# Schematic1.net
KiCad netlist of a schematic drawn in Altium Designer
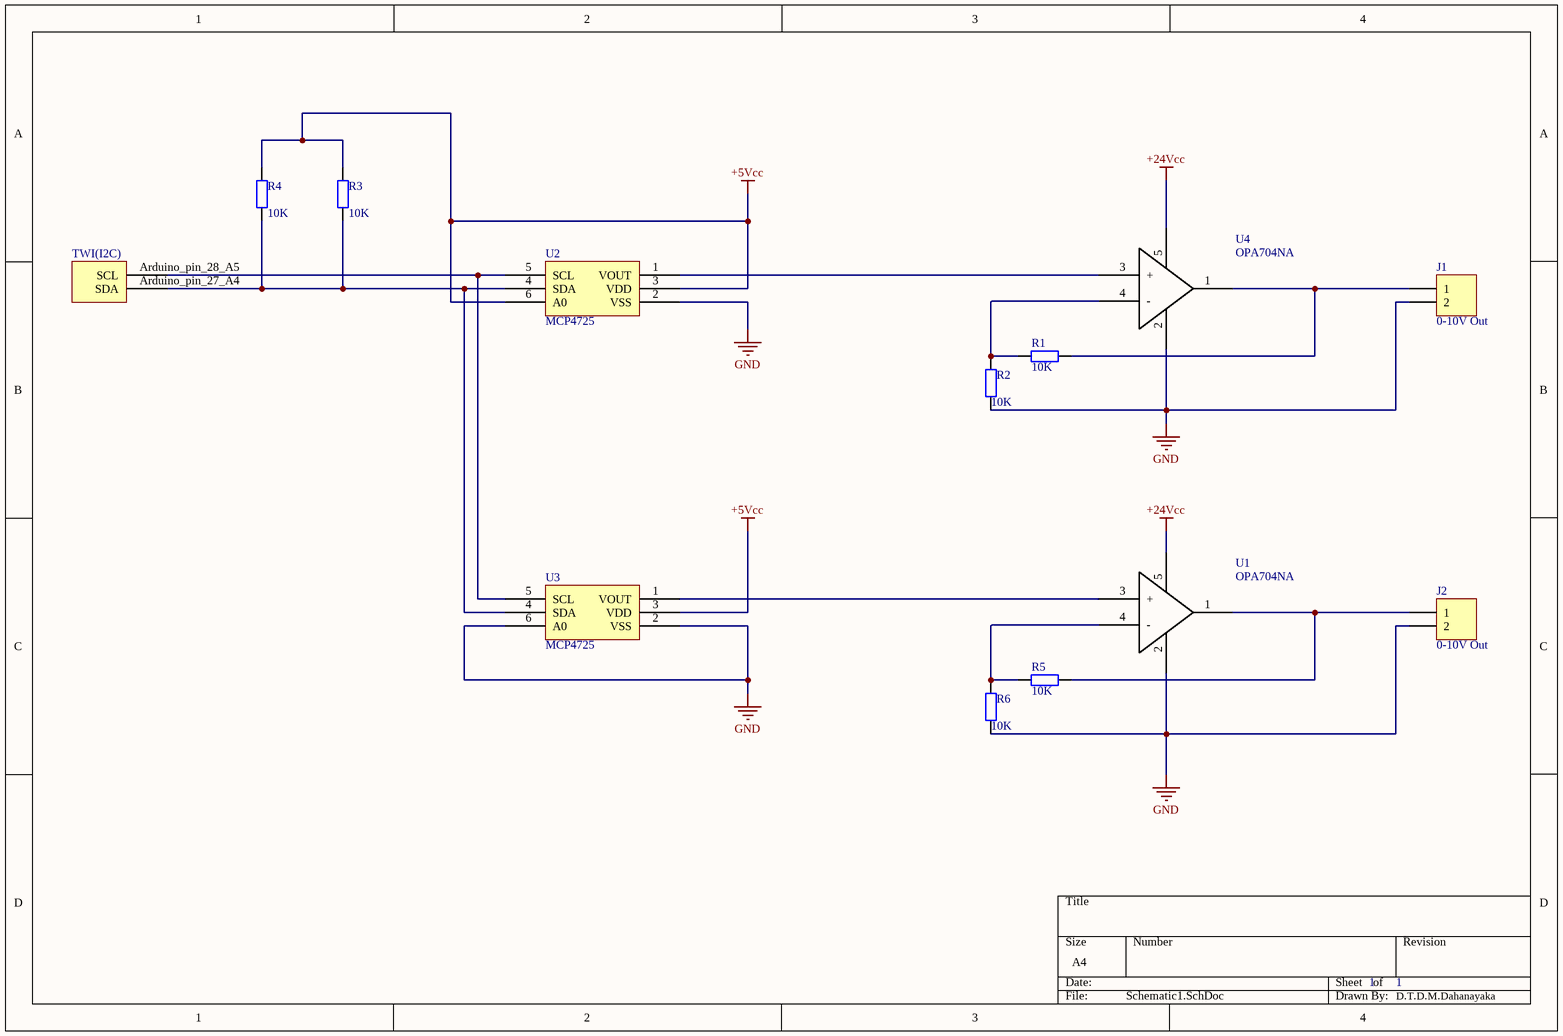
[diagram p0: Schematic1.SchDoc]

(export (version "E")
  (design (tool "Eeschema 10.0.6"))
  (components
    (comp (ref "J1")
      (value "0-10V Out")
      (footprint "HDR1X2")
      (description "Header, 2-Pin")
      (fields (field (name "PUBLISHER") "Altium Limited"))
      (libsource (lib "Miscellaneous Connectors") (part "Header 2"))
    )
    (comp (ref "J2")
      (value "0-10V Out")
      (footprint "HDR1X2")
      (description "Header, 2-Pin")
      (fields (field (name "PUBLISHER") "Altium Limited"))
      (libsource (lib "Miscellaneous Connectors") (part "Header 2"))
    )
    (comp (ref "R1")
      (value "10K")
      (footprint "AXIAL-0.4")
      (description "Resistor")
      (fields (field (name "Comment") "Res2") (field (name "PUBLISHER") "Altium Limited"))
      (libsource (lib "") (part "Res2_1"))
    )
    (comp (ref "R2")
      (value "10K")
      (footprint "AXIAL-0.4")
      (description "Resistor")
      (fields (field (name "Comment") "Res2") (field (name "PUBLISHER") "Altium Limited"))
      (libsource (lib "Miscellaneous Devices") (part "Res2"))
    )
    (comp (ref "R3")
      (value "10K")
      (footprint "AXIAL-0.4")
      (description "Resistor")
      (fields (field (name "Comment") "Res2") (field (name "PUBLISHER") "Altium Limited"))
      (libsource (lib "Miscellaneous Devices") (part "Res2"))
    )
    (comp (ref "R4")
      (value "10K")
      (footprint "AXIAL-0.4")
      (description "Resistor")
      (fields (field (name "Comment") "Res2") (field (name "PUBLISHER") "Altium Limited"))
      (libsource (lib "Miscellaneous Devices") (part "Res2"))
    )
    (comp (ref "R5")
      (value "10K")
      (footprint "AXIAL-0.4")
      (description "Resistor")
      (fields (field (name "Comment") "Res2") (field (name "PUBLISHER") "Altium Limited"))
      (libsource (lib "") (part "Res2_1"))
    )
    (comp (ref "R6")
      (value "10K")
      (footprint "AXIAL-0.4")
      (description "Resistor")
      (fields (field (name "Comment") "Res2") (field (name "PUBLISHER") "Altium Limited"))
      (libsource (lib "Miscellaneous Devices") (part "Res2"))
    )
    (comp (ref "TWI(I2C)")
      (value "Component_1")
      (libsource (lib "Arduino_mega_TWI_I2C") (part "Component_1"))
    )
    (comp (ref "U1") (value "OPA704NA") (libsource (lib "Op-Amp") (part "Component_1")))
    (comp (ref "U2") (value "MCP4725") (libsource (lib "MCP4725") (part "Component_1")))
    (comp (ref "U3") (value "MCP4725") (libsource (lib "MCP4725") (part "Component_1")))
    (comp (ref "U4") (value "OPA704NA") (libsource (lib "Op-Amp") (part "Component_1")))
  )
  (nets
    (net (code "1") (name "+5Vcc") (class "Default")
      (node (ref "R3") (pin "2") (pinfunction "2_2") (pintype "passive"))
      (node (ref "R4") (pin "2") (pinfunction "2_2") (pintype "passive"))
      (node (ref "U2") (pin "3") (pinfunction "VDD_3") (pintype "passive"))
      (node (ref "U2") (pin "6") (pinfunction "A0_6") (pintype "passive"))
      (node (ref "U3") (pin "3") (pinfunction "VDD_3") (pintype "passive"))
    )
    (net (code "2") (name "+24Vcc") (class "Default")
      (node (ref "U1") (pin "5") (pintype "passive"))
      (node (ref "U4") (pin "5") (pintype "passive"))
    )
    (net (code "3") (name "GND") (class "Default")
      (node (ref "J1") (pin "2") (pinfunction "2_2") (pintype "passive"))
      (node (ref "J2") (pin "2") (pinfunction "2_2") (pintype "passive"))
      (node (ref "R2") (pin "1") (pinfunction "1_1") (pintype "passive"))
      (node (ref "R6") (pin "1") (pinfunction "1_1") (pintype "passive"))
      (node (ref "U1") (pin "2") (pintype "passive"))
      (node (ref "U2") (pin "2") (pinfunction "VSS_2") (pintype "passive"))
      (node (ref "U3") (pin "2") (pinfunction "VSS_2") (pintype "passive"))
      (node (ref "U3") (pin "6") (pinfunction "A0_6") (pintype "passive"))
      (node (ref "U4") (pin "2") (pintype "passive"))
    )
    (net (code "4") (name "Net-(J1-Pad1)") (class "Default")
      (node (ref "J1") (pin "1") (pinfunction "1_1") (pintype "passive"))
      (node (ref "R1") (pin "1") (pinfunction "1_1") (pintype "passive"))
      (node (ref "U4") (pin "1") (pintype "passive"))
    )
    (net (code "5") (name "Net-(J2-Pad1)") (class "Default")
      (node (ref "J2") (pin "1") (pinfunction "1_1") (pintype "passive"))
      (node (ref "R5") (pin "1") (pinfunction "1_1") (pintype "passive"))
      (node (ref "U1") (pin "1") (pintype "passive"))
    )
    (net (code "6") (name "Net-(TWI(I2C)-SCL)") (class "Default")
      (node (ref "TWI(I2C)") (pin "Arduino_pin_28_A5") (pinfunction "SCL_Arduino_pin_28_A5") (pintype "passive"))
      (node (ref "U2") (pin "5") (pinfunction "SCL_5") (pintype "passive"))
      (node (ref "U3") (pin "5") (pinfunction "SCL_5") (pintype "passive"))
    )
    (net (code "7") (name "Net-(TWI(I2C)-SDA)") (class "Default")
      (node (ref "R3") (pin "1") (pinfunction "1_1") (pintype "passive"))
      (node (ref "R4") (pin "1") (pinfunction "1_1") (pintype "passive"))
      (node (ref "TWI(I2C)") (pin "Arduino_pin_27_A4") (pinfunction "SDA_Arduino_pin_27_A4") (pintype "passive"))
      (node (ref "U2") (pin "4") (pinfunction "SDA_4") (pintype "passive"))
      (node (ref "U3") (pin "4") (pinfunction "SDA_4") (pintype "passive"))
    )
    (net (code "8") (name "Net-(U1-+)") (class "Default")
      (node (ref "U1") (pin "3") (pinfunction "+_3") (pintype "passive"))
      (node (ref "U3") (pin "1") (pinfunction "VOUT_1") (pintype "passive"))
    )
    (net (code "9") (name "Net-(U1--)") (class "Default")
      (node (ref "R5") (pin "2") (pinfunction "2_2") (pintype "passive"))
      (node (ref "R6") (pin "2") (pinfunction "2_2") (pintype "passive"))
      (node (ref "U1") (pin "4") (pinfunction "-_4") (pintype "passive"))
    )
    (net (code "10") (name "Net-(U2-VOUT)") (class "Default")
      (node (ref "U2") (pin "1") (pinfunction "VOUT_1") (pintype "passive"))
      (node (ref "U4") (pin "3") (pinfunction "+_3") (pintype "passive"))
    )
    (net (code "11") (name "Net-(U4--)") (class "Default")
      (node (ref "R1") (pin "2") (pinfunction "2_2") (pintype "passive"))
      (node (ref "R2") (pin "2") (pinfunction "2_2") (pintype "passive"))
      (node (ref "U4") (pin "4") (pinfunction "-_4") (pintype "passive"))
    )
  )
)
